# oled-control-panel.net
KiCad netlist of a schematic drawn in EAGLE
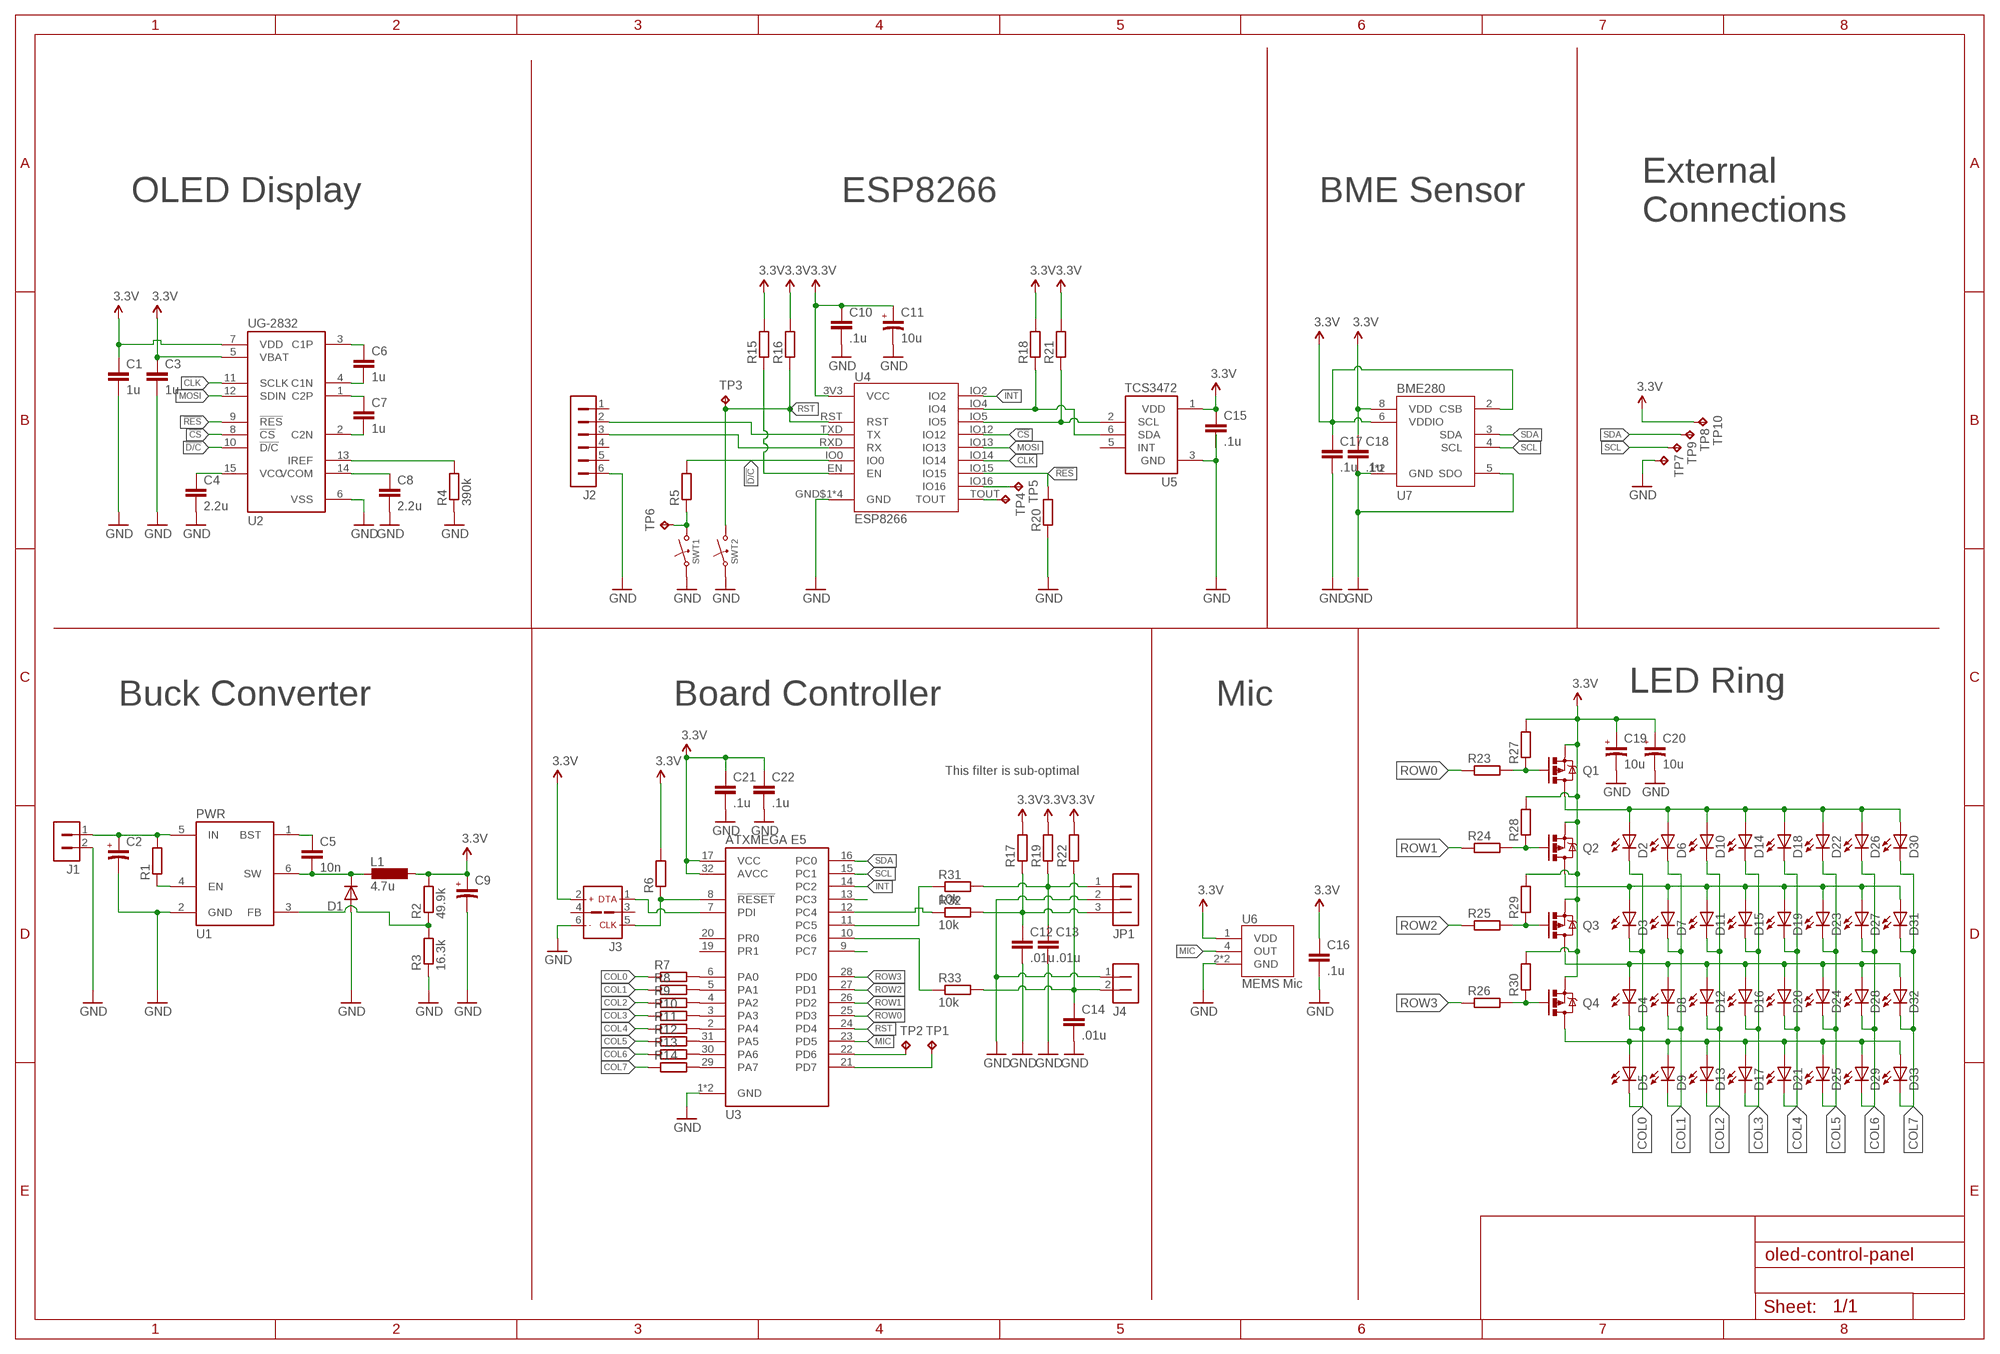
[diagram p0: schematic, sheet 1]

(export (version "E")
  (design (tool "Eeschema 10.0.6"))
  (components
    (comp (ref "C1")
      (value "1u")
      (footprint "eagle-import:0805")
      (libsource (lib "eagle-import") (part "C_0805"))
    )
    (comp (ref "C2")
      (value "C_POL_1206")
      (footprint "eagle-import:1206_POL")
      (libsource (lib "eagle-import") (part "C_POL_1206"))
    )
    (comp (ref "C3")
      (value "1u")
      (footprint "eagle-import:0805")
      (libsource (lib "eagle-import") (part "C_0805"))
    )
    (comp (ref "C4")
      (value "2.2u")
      (footprint "eagle-import:0805")
      (libsource (lib "eagle-import") (part "C_0805"))
    )
    (comp (ref "C5")
      (value "10n")
      (footprint "eagle-import:0805")
      (libsource (lib "eagle-import") (part "C_0805"))
    )
    (comp (ref "C6")
      (value "1u")
      (footprint "eagle-import:0805")
      (libsource (lib "eagle-import") (part "C_0805"))
    )
    (comp (ref "C7")
      (value "1u")
      (footprint "eagle-import:0805")
      (libsource (lib "eagle-import") (part "C_0805"))
    )
    (comp (ref "C8")
      (value "2.2u")
      (footprint "eagle-import:0805")
      (libsource (lib "eagle-import") (part "C_0805"))
    )
    (comp (ref "C9")
      (value "C_POL_1206")
      (footprint "eagle-import:1206_POL")
      (libsource (lib "eagle-import") (part "C_POL_1206"))
    )
    (comp (ref "C10")
      (value ".1u")
      (footprint "eagle-import:0603")
      (libsource (lib "eagle-import") (part "C_0603"))
    )
    (comp (ref "C11")
      (value "10u")
      (footprint "eagle-import:1206_POL")
      (libsource (lib "eagle-import") (part "C_POL_1206"))
    )
    (comp (ref "C12")
      (value ".01u")
      (footprint "eagle-import:0805")
      (libsource (lib "eagle-import") (part "C_0805"))
    )
    (comp (ref "C13")
      (value ".01u")
      (footprint "eagle-import:0805")
      (libsource (lib "eagle-import") (part "C_0805"))
    )
    (comp (ref "C14")
      (value ".01u")
      (footprint "eagle-import:0805")
      (libsource (lib "eagle-import") (part "C_0805"))
    )
    (comp (ref "C15")
      (value ".1u")
      (footprint "eagle-import:0603")
      (libsource (lib "eagle-import") (part "C_0603"))
    )
    (comp (ref "C16")
      (value ".1u")
      (footprint "eagle-import:0603")
      (libsource (lib "eagle-import") (part "C_0603"))
    )
    (comp (ref "C17")
      (value ".1u")
      (footprint "eagle-import:0603")
      (libsource (lib "eagle-import") (part "C_0603"))
    )
    (comp (ref "C18")
      (value ".1u")
      (footprint "eagle-import:0603")
      (libsource (lib "eagle-import") (part "C_0603"))
    )
    (comp (ref "C19")
      (value "10u")
      (footprint "eagle-import:1206_POL")
      (libsource (lib "eagle-import") (part "C_POL_1206"))
    )
    (comp (ref "C20")
      (value "10u")
      (footprint "eagle-import:1206_POL")
      (libsource (lib "eagle-import") (part "C_POL_1206"))
    )
    (comp (ref "C21")
      (value ".1u")
      (footprint "eagle-import:0603")
      (libsource (lib "eagle-import") (part "C_0603"))
    )
    (comp (ref "C22")
      (value ".1u")
      (footprint "eagle-import:0603")
      (libsource (lib "eagle-import") (part "C_0603"))
    )
    (comp (ref "D1")
      (value "D_FM581X")
      (footprint "eagle-import:DO-214AC")
      (libsource (lib "eagle-import") (part "D_FM581X"))
    )
    (comp (ref "D2")
      (value "LED_0805")
      (footprint "eagle-import:0805_LED")
      (libsource (lib "eagle-import") (part "LED_0805"))
    )
    (comp (ref "D3")
      (value "LED_0805")
      (footprint "eagle-import:0805_LED")
      (libsource (lib "eagle-import") (part "LED_0805"))
    )
    (comp (ref "D4")
      (value "LED_0805")
      (footprint "eagle-import:0805_LED")
      (libsource (lib "eagle-import") (part "LED_0805"))
    )
    (comp (ref "D5")
      (value "LED_0805")
      (footprint "eagle-import:0805_LED")
      (libsource (lib "eagle-import") (part "LED_0805"))
    )
    (comp (ref "D6")
      (value "LED_0805")
      (footprint "eagle-import:0805_LED")
      (libsource (lib "eagle-import") (part "LED_0805"))
    )
    (comp (ref "D7")
      (value "LED_0805")
      (footprint "eagle-import:0805_LED")
      (libsource (lib "eagle-import") (part "LED_0805"))
    )
    (comp (ref "D8")
      (value "LED_0805")
      (footprint "eagle-import:0805_LED")
      (libsource (lib "eagle-import") (part "LED_0805"))
    )
    (comp (ref "D9")
      (value "LED_0805")
      (footprint "eagle-import:0805_LED")
      (libsource (lib "eagle-import") (part "LED_0805"))
    )
    (comp (ref "D10")
      (value "LED_0805")
      (footprint "eagle-import:0805_LED")
      (libsource (lib "eagle-import") (part "LED_0805"))
    )
    (comp (ref "D11")
      (value "LED_0805")
      (footprint "eagle-import:0805_LED")
      (libsource (lib "eagle-import") (part "LED_0805"))
    )
    (comp (ref "D12")
      (value "LED_0805")
      (footprint "eagle-import:0805_LED")
      (libsource (lib "eagle-import") (part "LED_0805"))
    )
    (comp (ref "D13")
      (value "LED_0805")
      (footprint "eagle-import:0805_LED")
      (libsource (lib "eagle-import") (part "LED_0805"))
    )
    (comp (ref "D14")
      (value "LED_0805")
      (footprint "eagle-import:0805_LED")
      (libsource (lib "eagle-import") (part "LED_0805"))
    )
    (comp (ref "D15")
      (value "LED_0805")
      (footprint "eagle-import:0805_LED")
      (libsource (lib "eagle-import") (part "LED_0805"))
    )
    (comp (ref "D16")
      (value "LED_0805")
      (footprint "eagle-import:0805_LED")
      (libsource (lib "eagle-import") (part "LED_0805"))
    )
    (comp (ref "D17")
      (value "LED_0805")
      (footprint "eagle-import:0805_LED")
      (libsource (lib "eagle-import") (part "LED_0805"))
    )
    (comp (ref "D18")
      (value "LED_0805")
      (footprint "eagle-import:0805_LED")
      (libsource (lib "eagle-import") (part "LED_0805"))
    )
    (comp (ref "D19")
      (value "LED_0805")
      (footprint "eagle-import:0805_LED")
      (libsource (lib "eagle-import") (part "LED_0805"))
    )
    (comp (ref "D20")
      (value "LED_0805")
      (footprint "eagle-import:0805_LED")
      (libsource (lib "eagle-import") (part "LED_0805"))
    )
    (comp (ref "D21")
      (value "LED_0805")
      (footprint "eagle-import:0805_LED")
      (libsource (lib "eagle-import") (part "LED_0805"))
    )
    (comp (ref "D22")
      (value "LED_0805")
      (footprint "eagle-import:0805_LED")
      (libsource (lib "eagle-import") (part "LED_0805"))
    )
    (comp (ref "D23")
      (value "LED_0805")
      (footprint "eagle-import:0805_LED")
      (libsource (lib "eagle-import") (part "LED_0805"))
    )
    (comp (ref "D24")
      (value "LED_0805")
      (footprint "eagle-import:0805_LED")
      (libsource (lib "eagle-import") (part "LED_0805"))
    )
    (comp (ref "D25")
      (value "LED_0805")
      (footprint "eagle-import:0805_LED")
      (libsource (lib "eagle-import") (part "LED_0805"))
    )
    (comp (ref "D26")
      (value "LED_0805")
      (footprint "eagle-import:0805_LED")
      (libsource (lib "eagle-import") (part "LED_0805"))
    )
    (comp (ref "D27")
      (value "LED_0805")
      (footprint "eagle-import:0805_LED")
      (libsource (lib "eagle-import") (part "LED_0805"))
    )
    (comp (ref "D28")
      (value "LED_0805")
      (footprint "eagle-import:0805_LED")
      (libsource (lib "eagle-import") (part "LED_0805"))
    )
    (comp (ref "D29")
      (value "LED_0805")
      (footprint "eagle-import:0805_LED")
      (libsource (lib "eagle-import") (part "LED_0805"))
    )
    (comp (ref "D30")
      (value "LED_0805")
      (footprint "eagle-import:0805_LED")
      (libsource (lib "eagle-import") (part "LED_0805"))
    )
    (comp (ref "D31")
      (value "LED_0805")
      (footprint "eagle-import:0805_LED")
      (libsource (lib "eagle-import") (part "LED_0805"))
    )
    (comp (ref "D32")
      (value "LED_0805")
      (footprint "eagle-import:0805_LED")
      (libsource (lib "eagle-import") (part "LED_0805"))
    )
    (comp (ref "D33")
      (value "LED_0805")
      (footprint "eagle-import:0805_LED")
      (libsource (lib "eagle-import") (part "LED_0805"))
    )
    (comp (ref "J1")
      (value "1X2_MOLEX_53254")
      (footprint "eagle-import:1X2_MOLEX_53254")
      (libsource (lib "eagle-import") (part "1X2_MOLEX_53254"))
    )
    (comp (ref "J2")
      (value "1X6_SMD_RIGHT")
      (footprint "eagle-import:1X6_SMD_RIGHT")
      (libsource (lib "eagle-import") (part "1X6_SMD_RIGHT"))
    )
    (comp (ref "J3")
      (value "PDI_SMD")
      (footprint "eagle-import:ISP_SMD")
      (libsource (lib "eagle-import") (part "PDI_SMD"))
    )
    (comp (ref "J4")
      (value "1X2_MOLEX_53254")
      (footprint "eagle-import:1X2_MOLEX_53254")
      (libsource (lib "eagle-import") (part "1X2_MOLEX_53254"))
    )
    (comp (ref "JP1")
      (value "1X3_MOLEX_53254")
      (footprint "eagle-import:1X3_MOLEX_53254")
      (libsource (lib "eagle-import") (part "1X3_MOLEX_53254"))
    )
    (comp (ref "L1")
      (value "4.7u")
      (footprint "eagle-import:1210")
      (libsource (lib "eagle-import") (part "L_1210"))
    )
    (comp (ref "Q1")
      (value "PMV160UP")
      (footprint "eagle-import:SOT23")
      (libsource (lib "eagle-import") (part "PMV160UP"))
    )
    (comp (ref "Q2")
      (value "PMV160UP")
      (footprint "eagle-import:SOT23")
      (libsource (lib "eagle-import") (part "PMV160UP"))
    )
    (comp (ref "Q3")
      (value "PMV160UP")
      (footprint "eagle-import:SOT23")
      (libsource (lib "eagle-import") (part "PMV160UP"))
    )
    (comp (ref "Q4")
      (value "PMV160UP")
      (footprint "eagle-import:SOT23")
      (libsource (lib "eagle-import") (part "PMV160UP"))
    )
    (comp (ref "R1")
      (value "R_0805")
      (footprint "eagle-import:0805")
      (libsource (lib "eagle-import") (part "R_0805"))
    )
    (comp (ref "R2")
      (value "49.9k")
      (footprint "eagle-import:0805")
      (libsource (lib "eagle-import") (part "R_0805"))
    )
    (comp (ref "R3")
      (value "16.3k")
      (footprint "eagle-import:0805")
      (libsource (lib "eagle-import") (part "R_0805"))
    )
    (comp (ref "R4")
      (value "390k")
      (footprint "eagle-import:0805")
      (libsource (lib "eagle-import") (part "R_0805"))
    )
    (comp (ref "R5")
      (value "R_0603")
      (footprint "eagle-import:0603")
      (libsource (lib "eagle-import") (part "R_0603"))
    )
    (comp (ref "R6")
      (value "R_0603")
      (footprint "eagle-import:0603")
      (libsource (lib "eagle-import") (part "R_0603"))
    )
    (comp (ref "R7")
      (value "R_0603")
      (footprint "eagle-import:0603")
      (libsource (lib "eagle-import") (part "R_0603"))
    )
    (comp (ref "R8")
      (value "R_0603")
      (footprint "eagle-import:0603")
      (libsource (lib "eagle-import") (part "R_0603"))
    )
    (comp (ref "R9")
      (value "R_0603")
      (footprint "eagle-import:0603")
      (libsource (lib "eagle-import") (part "R_0603"))
    )
    (comp (ref "R10")
      (value "R_0603")
      (footprint "eagle-import:0603")
      (libsource (lib "eagle-import") (part "R_0603"))
    )
    (comp (ref "R11")
      (value "R_0603")
      (footprint "eagle-import:0603")
      (libsource (lib "eagle-import") (part "R_0603"))
    )
    (comp (ref "R12")
      (value "R_0603")
      (footprint "eagle-import:0603")
      (libsource (lib "eagle-import") (part "R_0603"))
    )
    (comp (ref "R13")
      (value "R_0603")
      (footprint "eagle-import:0603")
      (libsource (lib "eagle-import") (part "R_0603"))
    )
    (comp (ref "R14")
      (value "R_0603")
      (footprint "eagle-import:0603")
      (libsource (lib "eagle-import") (part "R_0603"))
    )
    (comp (ref "R15")
      (value "R_0603")
      (footprint "eagle-import:0603")
      (libsource (lib "eagle-import") (part "R_0603"))
    )
    (comp (ref "R16")
      (value "R_0603")
      (footprint "eagle-import:0603")
      (libsource (lib "eagle-import") (part "R_0603"))
    )
    (comp (ref "R17")
      (value "R_0603")
      (footprint "eagle-import:0603")
      (libsource (lib "eagle-import") (part "R_0603"))
    )
    (comp (ref "R18")
      (value "R_0603")
      (footprint "eagle-import:0603")
      (libsource (lib "eagle-import") (part "R_0603"))
    )
    (comp (ref "R19")
      (value "R_0603")
      (footprint "eagle-import:0603")
      (libsource (lib "eagle-import") (part "R_0603"))
    )
    (comp (ref "R20")
      (value "R_0603")
      (footprint "eagle-import:0603")
      (libsource (lib "eagle-import") (part "R_0603"))
    )
    (comp (ref "R21")
      (value "R_0603")
      (footprint "eagle-import:0603")
      (libsource (lib "eagle-import") (part "R_0603"))
    )
    (comp (ref "R22")
      (value "R_0603")
      (footprint "eagle-import:0603")
      (libsource (lib "eagle-import") (part "R_0603"))
    )
    (comp (ref "R23")
      (value "R_0603")
      (footprint "eagle-import:0603")
      (libsource (lib "eagle-import") (part "R_0603"))
    )
    (comp (ref "R24")
      (value "R_0603")
      (footprint "eagle-import:0603")
      (libsource (lib "eagle-import") (part "R_0603"))
    )
    (comp (ref "R25")
      (value "R_0603")
      (footprint "eagle-import:0603")
      (libsource (lib "eagle-import") (part "R_0603"))
    )
    (comp (ref "R26")
      (value "R_0603")
      (footprint "eagle-import:0603")
      (libsource (lib "eagle-import") (part "R_0603"))
    )
    (comp (ref "R27")
      (value "R_0603")
      (footprint "eagle-import:0603")
      (libsource (lib "eagle-import") (part "R_0603"))
    )
    (comp (ref "R28")
      (value "R_0603")
      (footprint "eagle-import:0603")
      (libsource (lib "eagle-import") (part "R_0603"))
    )
    (comp (ref "R29")
      (value "R_0603")
      (footprint "eagle-import:0603")
      (libsource (lib "eagle-import") (part "R_0603"))
    )
    (comp (ref "R30")
      (value "R_0603")
      (footprint "eagle-import:0603")
      (libsource (lib "eagle-import") (part "R_0603"))
    )
    (comp (ref "R31")
      (value "10k")
      (footprint "eagle-import:0603")
      (libsource (lib "eagle-import") (part "R_0603"))
    )
    (comp (ref "R32")
      (value "10k")
      (footprint "eagle-import:0603")
      (libsource (lib "eagle-import") (part "R_0603"))
    )
    (comp (ref "R33")
      (value "10k")
      (footprint "eagle-import:0603")
      (libsource (lib "eagle-import") (part "R_0603"))
    )
    (comp (ref "SWT1")
      (value "BUTTON_SMD_2P")
      (footprint "eagle-import:BTN_SMD_2PIN")
      (libsource (lib "eagle-import") (part "BUTTON_SMD_2P"))
    )
    (comp (ref "SWT2")
      (value "BUTTON_SMD_2P")
      (footprint "eagle-import:BTN_SMD_2PIN")
      (libsource (lib "eagle-import") (part "BUTTON_SMD_2P"))
    )
    (comp (ref "TP1")
      (value "TPTP15R")
      (footprint "eagle-import:TP15R")
      (libsource (lib "eagle-import") (part "TPTP15R"))
    )
    (comp (ref "TP2")
      (value "TPTP15R")
      (footprint "eagle-import:TP15R")
      (libsource (lib "eagle-import") (part "TPTP15R"))
    )
    (comp (ref "TP3")
      (value "TPTP15R")
      (footprint "eagle-import:TP15R")
      (libsource (lib "eagle-import") (part "TPTP15R"))
    )
    (comp (ref "TP4")
      (value "TPTP15R")
      (footprint "eagle-import:TP15R")
      (libsource (lib "eagle-import") (part "TPTP15R"))
    )
    (comp (ref "TP5")
      (value "TPTP15R")
      (footprint "eagle-import:TP15R")
      (libsource (lib "eagle-import") (part "TPTP15R"))
    )
    (comp (ref "TP6")
      (value "TPTP15R")
      (footprint "eagle-import:TP15R")
      (libsource (lib "eagle-import") (part "TPTP15R"))
    )
    (comp (ref "TP7")
      (value "TPTP15R")
      (footprint "eagle-import:TP15R")
      (libsource (lib "eagle-import") (part "TPTP15R"))
    )
    (comp (ref "TP8")
      (value "TPTP15R")
      (footprint "eagle-import:TP15R")
      (libsource (lib "eagle-import") (part "TPTP15R"))
    )
    (comp (ref "TP9")
      (value "TPTP15R")
      (footprint "eagle-import:TP15R")
      (libsource (lib "eagle-import") (part "TPTP15R"))
    )
    (comp (ref "TP10")
      (value "TPTP15R")
      (footprint "eagle-import:TP15R")
      (libsource (lib "eagle-import") (part "TPTP15R"))
    )
    (comp (ref "U1")
      (value "AP3211")
      (footprint "eagle-import:SOT23-6")
      (libsource (lib "eagle-import") (part "AP3211"))
    )
    (comp (ref "U2")
      (value "UG-2832HSWEG04")
      (footprint "eagle-import:UG-2832HSWEG04")
      (libsource (lib "eagle-import") (part "UG-2832HSWEG04"))
    )
    (comp (ref "U3")
      (value "ATXMEGA_E5_TQFP")
      (footprint "eagle-import:TQFP32")
      (libsource (lib "eagle-import") (part "ATXMEGA_E5_TQFP"))
    )
    (comp (ref "U4")
      (value "ESP8266_13")
      (footprint "eagle-import:ESP13")
      (libsource (lib "eagle-import") (part "ESP8266_13"))
    )
    (comp (ref "U5")
      (value "TCS3472")
      (footprint "eagle-import:TCS3472")
      (libsource (lib "eagle-import") (part "TCS3472"))
    )
    (comp (ref "U6")
      (value "SPW2430HR5H_B")
      (footprint "eagle-import:SPW2430HR5H_B")
      (libsource (lib "eagle-import") (part "SPW2430HR5H_B"))
    )
    (comp (ref "U7")
      (value "BME280")
      (footprint "eagle-import:BME280")
      (libsource (lib "eagle-import") (part "BME280"))
    )
  )
  (nets
    (net (code "1") (name "/~{CS}") (class "Default")
      (node (ref "U2") (pin "8") (pinfunction "~{CS}_8") (pintype "bidirectional"))
      (node (ref "U4") (pin "IO12") (pinfunction "IO12_IO12") (pintype "bidirectional"))
    )
    (net (code "2") (name "/~{D{slash}C}") (class "Default")
      (node (ref "R5") (pin "2") (pinfunction "2_2") (pintype "passive"))
      (node (ref "U2") (pin "10") (pinfunction "~{D/C}_10") (pintype "bidirectional"))
      (node (ref "U4") (pin "IO0") (pinfunction "IO0_IO0") (pintype "bidirectional"))
    )
    (net (code "3") (name "/~{RES}") (class "Default")
      (node (ref "R20") (pin "2") (pinfunction "2_2") (pintype "passive"))
      (node (ref "U2") (pin "9") (pinfunction "~{RES}_9") (pintype "bidirectional"))
      (node (ref "U4") (pin "IO15") (pinfunction "IO15_IO15") (pintype "bidirectional"))
    )
    (net (code "4") (name "3.3V") (class "Default")
      (node (ref "C1") (pin "1") (pinfunction "1_1") (pintype "passive"))
      (node (ref "C10") (pin "1") (pinfunction "1_1") (pintype "passive"))
      (node (ref "C11") (pin "1") (pinfunction "1_1") (pintype "passive"))
      (node (ref "C15") (pin "1") (pinfunction "1_1") (pintype "passive"))
      (node (ref "C16") (pin "1") (pinfunction "1_1") (pintype "passive"))
      (node (ref "C17") (pin "1") (pinfunction "1_1") (pintype "passive"))
      (node (ref "C18") (pin "1") (pinfunction "1_1") (pintype "passive"))
      (node (ref "C19") (pin "1") (pinfunction "1_1") (pintype "passive"))
      (node (ref "C20") (pin "1") (pinfunction "1_1") (pintype "passive"))
      (node (ref "C21") (pin "1") (pinfunction "1_1") (pintype "passive"))
      (node (ref "C22") (pin "1") (pinfunction "1_1") (pintype "passive"))
      (node (ref "C3") (pin "1") (pinfunction "1_1") (pintype "passive"))
      (node (ref "C9") (pin "1") (pinfunction "1_1") (pintype "passive"))
      (node (ref "J3") (pin "2") (pinfunction "VCC_2") (pintype "bidirectional"))
      (node (ref "L1") (pin "2") (pinfunction "2_2") (pintype "passive"))
      (node (ref "Q1") (pin "2") (pinfunction "S_2") (pintype "passive"))
      (node (ref "Q2") (pin "2") (pinfunction "S_2") (pintype "passive"))
      (node (ref "Q3") (pin "2") (pinfunction "S_2") (pintype "passive"))
      (node (ref "Q4") (pin "2") (pinfunction "S_2") (pintype "passive"))
      (node (ref "R15") (pin "2") (pinfunction "2_2") (pintype "passive"))
      (node (ref "R16") (pin "2") (pinfunction "2_2") (pintype "passive"))
      (node (ref "R17") (pin "2") (pinfunction "2_2") (pintype "passive"))
      (node (ref "R18") (pin "2") (pinfunction "2_2") (pintype "passive"))
      (node (ref "R19") (pin "2") (pinfunction "2_2") (pintype "passive"))
      (node (ref "R2") (pin "2") (pinfunction "2_2") (pintype "passive"))
      (node (ref "R21") (pin "2") (pinfunction "2_2") (pintype "passive"))
      (node (ref "R22") (pin "2") (pinfunction "2_2") (pintype "passive"))
      (node (ref "R27") (pin "2") (pinfunction "2_2") (pintype "passive"))
      (node (ref "R28") (pin "2") (pinfunction "2_2") (pintype "passive"))
      (node (ref "R29") (pin "2") (pinfunction "2_2") (pintype "passive"))
      (node (ref "R30") (pin "2") (pinfunction "2_2") (pintype "passive"))
      (node (ref "R6") (pin "2") (pinfunction "2_2") (pintype "passive"))
      (node (ref "TP10") (pin "TP") (pinfunction "TP_TP") (pintype "input"))
      (node (ref "U2") (pin "5") (pinfunction "VBAT_5") (pintype "bidirectional"))
      (node (ref "U2") (pin "7") (pinfunction "VDD_7") (pintype "bidirectional"))
      (node (ref "U3") (pin "17") (pinfunction "VCC_17") (pintype "bidirectional"))
      (node (ref "U3") (pin "32") (pinfunction "AVCC_32") (pintype "bidirectional"))
      (node (ref "U4") (pin "3V3") (pinfunction "VCC_3V3") (pintype "bidirectional"))
      (node (ref "U5") (pin "1") (pinfunction "VDD_1") (pintype "bidirectional"))
      (node (ref "U6") (pin "1") (pinfunction "VDD_1") (pintype "bidirectional"))
      (node (ref "U7") (pin "2") (pinfunction "CSB_2") (pintype "bidirectional"))
      (node (ref "U7") (pin "6") (pinfunction "VDDIO_6") (pintype "bidirectional"))
      (node (ref "U7") (pin "8") (pinfunction "VDD_8") (pintype "bidirectional"))
    )
    (net (code "5") (name "CLK") (class "Default")
      (node (ref "U2") (pin "11") (pinfunction "SCLK_11") (pintype "bidirectional"))
      (node (ref "U4") (pin "IO14") (pinfunction "IO14_IO14") (pintype "bidirectional"))
    )
    (net (code "6") (name "COL0") (class "Default")
      (node (ref "D2") (pin "C") (pinfunction "C_C") (pintype "passive"))
      (node (ref "D3") (pin "C") (pinfunction "C_C") (pintype "passive"))
      (node (ref "D4") (pin "C") (pinfunction "C_C") (pintype "passive"))
      (node (ref "D5") (pin "C") (pinfunction "C_C") (pintype "passive"))
      (node (ref "R7") (pin "1") (pinfunction "1_1") (pintype "passive"))
    )
    (net (code "7") (name "COL1") (class "Default")
      (node (ref "D6") (pin "C") (pinfunction "C_C") (pintype "passive"))
      (node (ref "D7") (pin "C") (pinfunction "C_C") (pintype "passive"))
      (node (ref "D8") (pin "C") (pinfunction "C_C") (pintype "passive"))
      (node (ref "D9") (pin "C") (pinfunction "C_C") (pintype "passive"))
      (node (ref "R8") (pin "1") (pinfunction "1_1") (pintype "passive"))
    )
    (net (code "8") (name "COL2") (class "Default")
      (node (ref "D10") (pin "C") (pinfunction "C_C") (pintype "passive"))
      (node (ref "D11") (pin "C") (pinfunction "C_C") (pintype "passive"))
      (node (ref "D12") (pin "C") (pinfunction "C_C") (pintype "passive"))
      (node (ref "D13") (pin "C") (pinfunction "C_C") (pintype "passive"))
      (node (ref "R9") (pin "1") (pinfunction "1_1") (pintype "passive"))
    )
    (net (code "9") (name "COL3") (class "Default")
      (node (ref "D14") (pin "C") (pinfunction "C_C") (pintype "passive"))
      (node (ref "D15") (pin "C") (pinfunction "C_C") (pintype "passive"))
      (node (ref "D16") (pin "C") (pinfunction "C_C") (pintype "passive"))
      (node (ref "D17") (pin "C") (pinfunction "C_C") (pintype "passive"))
      (node (ref "R10") (pin "1") (pinfunction "1_1") (pintype "passive"))
    )
    (net (code "10") (name "COL4") (class "Default")
      (node (ref "D18") (pin "C") (pinfunction "C_C") (pintype "passive"))
      (node (ref "D19") (pin "C") (pinfunction "C_C") (pintype "passive"))
      (node (ref "D20") (pin "C") (pinfunction "C_C") (pintype "passive"))
      (node (ref "D21") (pin "C") (pinfunction "C_C") (pintype "passive"))
      (node (ref "R11") (pin "1") (pinfunction "1_1") (pintype "passive"))
    )
    (net (code "11") (name "COL5") (class "Default")
      (node (ref "D22") (pin "C") (pinfunction "C_C") (pintype "passive"))
      (node (ref "D23") (pin "C") (pinfunction "C_C") (pintype "passive"))
      (node (ref "D24") (pin "C") (pinfunction "C_C") (pintype "passive"))
      (node (ref "D25") (pin "C") (pinfunction "C_C") (pintype "passive"))
      (node (ref "R12") (pin "1") (pinfunction "1_1") (pintype "passive"))
    )
    (net (code "12") (name "COL6") (class "Default")
      (node (ref "D26") (pin "C") (pinfunction "C_C") (pintype "passive"))
      (node (ref "D27") (pin "C") (pinfunction "C_C") (pintype "passive"))
      (node (ref "D28") (pin "C") (pinfunction "C_C") (pintype "passive"))
      (node (ref "D29") (pin "C") (pinfunction "C_C") (pintype "passive"))
      (node (ref "R13") (pin "1") (pinfunction "1_1") (pintype "passive"))
    )
    (net (code "13") (name "COL7") (class "Default")
      (node (ref "D30") (pin "C") (pinfunction "C_C") (pintype "passive"))
      (node (ref "D31") (pin "C") (pinfunction "C_C") (pintype "passive"))
      (node (ref "D32") (pin "C") (pinfunction "C_C") (pintype "passive"))
      (node (ref "D33") (pin "C") (pinfunction "C_C") (pintype "passive"))
      (node (ref "R14") (pin "1") (pinfunction "1_1") (pintype "passive"))
    )
    (net (code "14") (name "GND") (class "Default")
      (node (ref "C1") (pin "2") (pinfunction "2_2") (pintype "passive"))
      (node (ref "C10") (pin "2") (pinfunction "2_2") (pintype "passive"))
      (node (ref "C11") (pin "2") (pinfunction "2_2") (pintype "passive"))
      (node (ref "C12") (pin "2") (pinfunction "2_2") (pintype "passive"))
      (node (ref "C13") (pin "2") (pinfunction "2_2") (pintype "passive"))
      (node (ref "C14") (pin "2") (pinfunction "2_2") (pintype "passive"))
      (node (ref "C15") (pin "2") (pinfunction "2_2") (pintype "passive"))
      (node (ref "C16") (pin "2") (pinfunction "2_2") (pintype "passive"))
      (node (ref "C17") (pin "2") (pinfunction "2_2") (pintype "passive"))
      (node (ref "C18") (pin "2") (pinfunction "2_2") (pintype "passive"))
      (node (ref "C19") (pin "2") (pinfunction "2_2") (pintype "passive"))
      (node (ref "C2") (pin "2") (pinfunction "2_2") (pintype "passive"))
      (node (ref "C20") (pin "2") (pinfunction "2_2") (pintype "passive"))
      (node (ref "C21") (pin "2") (pinfunction "2_2") (pintype "passive"))
      (node (ref "C22") (pin "2") (pinfunction "2_2") (pintype "passive"))
      (node (ref "C3") (pin "2") (pinfunction "2_2") (pintype "passive"))
      (node (ref "C4") (pin "2") (pinfunction "2_2") (pintype "passive"))
      (node (ref "C8") (pin "2") (pinfunction "2_2") (pintype "passive"))
      (node (ref "C9") (pin "2") (pinfunction "2_2") (pintype "passive"))
      (node (ref "D1") (pin "A") (pinfunction "A_A") (pintype "passive"))
      (node (ref "J1") (pin "2") (pinfunction "2_2") (pintype "bidirectional"))
      (node (ref "J2") (pin "6") (pinfunction "6_6") (pintype "bidirectional"))
      (node (ref "J3") (pin "6") (pinfunction "GND_6") (pintype "bidirectional"))
      (node (ref "J4") (pin "1") (pinfunction "1_1") (pintype "bidirectional"))
      (node (ref "JP1") (pin "2") (pinfunction "2_2") (pintype "bidirectional"))
      (node (ref "R20") (pin "1") (pinfunction "1_1") (pintype "passive"))
      (node (ref "R3") (pin "1") (pinfunction "1_1") (pintype "passive"))
      (node (ref "R4") (pin "1") (pinfunction "1_1") (pintype "passive"))
      (node (ref "SWT1") (pin "1") (pinfunction "P$1_1") (pintype "bidirectional"))
      (node (ref "SWT2") (pin "1") (pinfunction "P$1_1") (pintype "bidirectional"))
      (node (ref "TP7") (pin "TP") (pinfunction "TP_TP") (pintype "input"))
      (node (ref "U1") (pin "2") (pinfunction "GND_2") (pintype "bidirectional"))
      (node (ref "U2") (pin "6") (pinfunction "VSS_6") (pintype "bidirectional"))
      (node (ref "U3") (pin "1") (pinfunction "GND_1") (pintype "bidirectional"))
      (node (ref "U3") (pin "18") (pinfunction "GND_18") (pintype "bidirectional"))
      (node (ref "U4") (pin "GND$1") (pinfunction "GND_GND$1") (pintype "bidirectional"))
      (node (ref "U4") (pin "GND$2") (pinfunction "GND_GND$2") (pintype "bidirectional"))
      (node (ref "U4") (pin "GND$3") (pinfunction "GND_GND$3") (pintype "bidirectional"))
      (node (ref "U4") (pin "GND$4") (pinfunction "GND_GND$4") (pintype "bidirectional"))
      (node (ref "U5") (pin "3") (pinfunction "GND_3") (pintype "bidirectional"))
      (node (ref "U6") (pin "2") (pinfunction "GND_2") (pintype "bidirectional"))
      (node (ref "U6") (pin "3") (pinfunction "GND_3") (pintype "bidirectional"))
      (node (ref "U7") (pin "1") (pinfunction "GND_1") (pintype "bidirectional"))
      (node (ref "U7") (pin "5") (pinfunction "SDO_5") (pintype "bidirectional"))
      (node (ref "U7") (pin "7") (pinfunction "GND_7") (pintype "bidirectional"))
    )
    (net (code "15") (name "INT") (class "Default")
      (node (ref "U3") (pin "14") (pinfunction "PC2_14") (pintype "bidirectional"))
      (node (ref "U4") (pin "IO2") (pinfunction "IO2_IO2") (pintype "bidirectional"))
    )
    (net (code "16") (name "MIC") (class "Default")
      (node (ref "U3") (pin "23") (pinfunction "PD5_23") (pintype "bidirectional"))
      (node (ref "U6") (pin "4") (pinfunction "OUT_4") (pintype "bidirectional"))
    )
    (net (code "17") (name "MOSI") (class "Default")
      (node (ref "U2") (pin "12") (pinfunction "SDIN_12") (pintype "bidirectional"))
      (node (ref "U4") (pin "IO13") (pinfunction "IO13_IO13") (pintype "bidirectional"))
    )
    (net (code "18") (name "Net-(C12-Pad1)") (class "Default")
      (node (ref "C12") (pin "1") (pinfunction "1_1") (pintype "passive"))
      (node (ref "JP1") (pin "3") (pinfunction "3_3") (pintype "bidirectional"))
      (node (ref "R17") (pin "1") (pinfunction "1_1") (pintype "passive"))
      (node (ref "R32") (pin "2") (pinfunction "2_2") (pintype "passive"))
    )
    (net (code "19") (name "Net-(C13-Pad1)") (class "Default")
      (node (ref "C13") (pin "1") (pinfunction "1_1") (pintype "passive"))
      (node (ref "JP1") (pin "1") (pinfunction "1_1") (pintype "bidirectional"))
      (node (ref "R19") (pin "1") (pinfunction "1_1") (pintype "passive"))
      (node (ref "R31") (pin "2") (pinfunction "2_2") (pintype "passive"))
    )
    (net (code "20") (name "Net-(C14-Pad1)") (class "Default")
      (node (ref "C14") (pin "1") (pinfunction "1_1") (pintype "passive"))
      (node (ref "J4") (pin "2") (pinfunction "2_2") (pintype "bidirectional"))
      (node (ref "R22") (pin "1") (pinfunction "1_1") (pintype "passive"))
      (node (ref "R33") (pin "2") (pinfunction "2_2") (pintype "passive"))
    )
    (net (code "21") (name "Net-(J3-CLK)") (class "Default")
      (node (ref "J3") (pin "5") (pinfunction "CLK_5") (pintype "bidirectional"))
      (node (ref "R6") (pin "1") (pinfunction "1_1") (pintype "passive"))
      (node (ref "U3") (pin "8") (pinfunction "~{RESET}_8") (pintype "bidirectional"))
    )
    (net (code "22") (name "Net-(J3-DATA)") (class "Default")
      (node (ref "J3") (pin "1") (pinfunction "DATA_1") (pintype "bidirectional"))
      (node (ref "U3") (pin "7") (pinfunction "PDI_7") (pintype "bidirectional"))
    )
    (net (code "23") (name "Net-(Q1-D)") (class "Default")
      (node (ref "D10") (pin "A") (pinfunction "A_A") (pintype "passive"))
      (node (ref "D14") (pin "A") (pinfunction "A_A") (pintype "passive"))
      (node (ref "D18") (pin "A") (pinfunction "A_A") (pintype "passive"))
      (node (ref "D2") (pin "A") (pinfunction "A_A") (pintype "passive"))
      (node (ref "D22") (pin "A") (pinfunction "A_A") (pintype "passive"))
      (node (ref "D26") (pin "A") (pinfunction "A_A") (pintype "passive"))
      (node (ref "D30") (pin "A") (pinfunction "A_A") (pintype "passive"))
      (node (ref "D6") (pin "A") (pinfunction "A_A") (pintype "passive"))
      (node (ref "Q1") (pin "3") (pinfunction "D_3") (pintype "passive"))
    )
    (net (code "24") (name "Net-(Q1-G)") (class "Default")
      (node (ref "Q1") (pin "1") (pinfunction "G_1") (pintype "passive"))
      (node (ref "R23") (pin "2") (pinfunction "2_2") (pintype "passive"))
      (node (ref "R27") (pin "1") (pinfunction "1_1") (pintype "passive"))
    )
    (net (code "25") (name "Net-(Q2-D)") (class "Default")
      (node (ref "D11") (pin "A") (pinfunction "A_A") (pintype "passive"))
      (node (ref "D15") (pin "A") (pinfunction "A_A") (pintype "passive"))
      (node (ref "D19") (pin "A") (pinfunction "A_A") (pintype "passive"))
      (node (ref "D23") (pin "A") (pinfunction "A_A") (pintype "passive"))
      (node (ref "D27") (pin "A") (pinfunction "A_A") (pintype "passive"))
      (node (ref "D3") (pin "A") (pinfunction "A_A") (pintype "passive"))
      (node (ref "D31") (pin "A") (pinfunction "A_A") (pintype "passive"))
      (node (ref "D7") (pin "A") (pinfunction "A_A") (pintype "passive"))
      (node (ref "Q2") (pin "3") (pinfunction "D_3") (pintype "passive"))
    )
    (net (code "26") (name "Net-(Q2-G)") (class "Default")
      (node (ref "Q2") (pin "1") (pinfunction "G_1") (pintype "passive"))
      (node (ref "R24") (pin "2") (pinfunction "2_2") (pintype "passive"))
      (node (ref "R28") (pin "1") (pinfunction "1_1") (pintype "passive"))
    )
    (net (code "27") (name "Net-(Q3-D)") (class "Default")
      (node (ref "D12") (pin "A") (pinfunction "A_A") (pintype "passive"))
      (node (ref "D16") (pin "A") (pinfunction "A_A") (pintype "passive"))
      (node (ref "D20") (pin "A") (pinfunction "A_A") (pintype "passive"))
      (node (ref "D24") (pin "A") (pinfunction "A_A") (pintype "passive"))
      (node (ref "D28") (pin "A") (pinfunction "A_A") (pintype "passive"))
      (node (ref "D32") (pin "A") (pinfunction "A_A") (pintype "passive"))
      (node (ref "D4") (pin "A") (pinfunction "A_A") (pintype "passive"))
      (node (ref "D8") (pin "A") (pinfunction "A_A") (pintype "passive"))
      (node (ref "Q3") (pin "3") (pinfunction "D_3") (pintype "passive"))
    )
    (net (code "28") (name "Net-(Q3-G)") (class "Default")
      (node (ref "Q3") (pin "1") (pinfunction "G_1") (pintype "passive"))
      (node (ref "R25") (pin "2") (pinfunction "2_2") (pintype "passive"))
      (node (ref "R29") (pin "1") (pinfunction "1_1") (pintype "passive"))
    )
    (net (code "29") (name "Net-(Q4-D)") (class "Default")
      (node (ref "D13") (pin "A") (pinfunction "A_A") (pintype "passive"))
      (node (ref "D17") (pin "A") (pinfunction "A_A") (pintype "passive"))
      (node (ref "D21") (pin "A") (pinfunction "A_A") (pintype "passive"))
      (node (ref "D25") (pin "A") (pinfunction "A_A") (pintype "passive"))
      (node (ref "D29") (pin "A") (pinfunction "A_A") (pintype "passive"))
      (node (ref "D33") (pin "A") (pinfunction "A_A") (pintype "passive"))
      (node (ref "D5") (pin "A") (pinfunction "A_A") (pintype "passive"))
      (node (ref "D9") (pin "A") (pinfunction "A_A") (pintype "passive"))
      (node (ref "Q4") (pin "3") (pinfunction "D_3") (pintype "passive"))
    )
    (net (code "30") (name "Net-(Q4-G)") (class "Default")
      (node (ref "Q4") (pin "1") (pinfunction "G_1") (pintype "passive"))
      (node (ref "R26") (pin "2") (pinfunction "2_2") (pintype "passive"))
      (node (ref "R30") (pin "1") (pinfunction "1_1") (pintype "passive"))
    )
    (net (code "31") (name "Net-(R15-Pad1)") (class "Default")
      (node (ref "R15") (pin "1") (pinfunction "1_1") (pintype "passive"))
      (node (ref "U4") (pin "EN") (pinfunction "EN_EN") (pintype "bidirectional"))
    )
    (net (code "32") (name "Net-(SWT1-P$2)") (class "Default")
      (node (ref "R5") (pin "1") (pinfunction "1_1") (pintype "passive"))
      (node (ref "SWT1") (pin "2") (pinfunction "P$2_2") (pintype "bidirectional"))
      (node (ref "TP6") (pin "TP") (pinfunction "TP_TP") (pintype "input"))
    )
    (net (code "33") (name "Net-(TP4-PadTP)") (class "Default")
      (node (ref "TP4") (pin "TP") (pinfunction "TP_TP") (pintype "input"))
      (node (ref "U4") (pin "TOUT") (pinfunction "TOUT_TOUT") (pintype "bidirectional"))
    )
    (net (code "34") (name "Net-(TP5-PadTP)") (class "Default")
      (node (ref "TP5") (pin "TP") (pinfunction "TP_TP") (pintype "input"))
      (node (ref "U4") (pin "IO16") (pinfunction "IO16_IO16") (pintype "bidirectional"))
    )
    (net (code "35") (name "Net-(U1-BST)") (class "Default")
      (node (ref "C5") (pin "1") (pinfunction "1_1") (pintype "passive"))
      (node (ref "U1") (pin "1") (pinfunction "BST_1") (pintype "bidirectional"))
    )
    (net (code "36") (name "Net-(U1-EN)") (class "Default")
      (node (ref "R1") (pin "1") (pinfunction "1_1") (pintype "passive"))
      (node (ref "U1") (pin "4") (pinfunction "EN_4") (pintype "bidirectional"))
    )
    (net (code "37") (name "Net-(U1-FB)") (class "Default")
      (node (ref "R2") (pin "1") (pinfunction "1_1") (pintype "passive"))
      (node (ref "R3") (pin "2") (pinfunction "2_2") (pintype "passive"))
      (node (ref "U1") (pin "3") (pinfunction "FB_3") (pintype "bidirectional"))
    )
    (net (code "38") (name "Net-(U1-IN)") (class "Default")
      (node (ref "C2") (pin "1") (pinfunction "1_1") (pintype "passive"))
      (node (ref "J1") (pin "1") (pinfunction "1_1") (pintype "bidirectional"))
      (node (ref "R1") (pin "2") (pinfunction "2_2") (pintype "passive"))
      (node (ref "U1") (pin "5") (pinfunction "IN_5") (pintype "bidirectional"))
    )
    (net (code "39") (name "Net-(U1-SW)") (class "Default")
      (node (ref "C5") (pin "2") (pinfunction "2_2") (pintype "passive"))
      (node (ref "D1") (pin "C") (pinfunction "C_C") (pintype "passive"))
      (node (ref "L1") (pin "1") (pinfunction "1_1") (pintype "passive"))
      (node (ref "U1") (pin "6") (pinfunction "SW_6") (pintype "bidirectional"))
    )
    (net (code "40") (name "Net-(U2-C1N)") (class "Default")
      (node (ref "C6") (pin "2") (pinfunction "2_2") (pintype "passive"))
      (node (ref "U2") (pin "4") (pinfunction "C1N_4") (pintype "bidirectional"))
    )
    (net (code "41") (name "Net-(U2-C1P)") (class "Default")
      (node (ref "C6") (pin "1") (pinfunction "1_1") (pintype "passive"))
      (node (ref "U2") (pin "3") (pinfunction "C1P_3") (pintype "bidirectional"))
    )
    (net (code "42") (name "Net-(U2-C2N)") (class "Default")
      (node (ref "C7") (pin "2") (pinfunction "2_2") (pintype "passive"))
      (node (ref "U2") (pin "2") (pinfunction "C2N_2") (pintype "bidirectional"))
    )
    (net (code "43") (name "Net-(U2-C2P)") (class "Default")
      (node (ref "C7") (pin "1") (pinfunction "1_1") (pintype "passive"))
      (node (ref "U2") (pin "1") (pinfunction "C2P_1") (pintype "bidirectional"))
    )
    (net (code "44") (name "Net-(U2-IREF)") (class "Default")
      (node (ref "R4") (pin "2") (pinfunction "2_2") (pintype "passive"))
      (node (ref "U2") (pin "13") (pinfunction "IREF_13") (pintype "bidirectional"))
    )
    (net (code "45") (name "Net-(U2-VCC)") (class "Default")
      (node (ref "C4") (pin "1") (pinfunction "1_1") (pintype "passive"))
      (node (ref "U2") (pin "15") (pinfunction "VCC_15") (pintype "bidirectional"))
    )
    (net (code "46") (name "Net-(U2-VCOM)") (class "Default")
      (node (ref "C8") (pin "1") (pinfunction "1_1") (pintype "passive"))
      (node (ref "U2") (pin "14") (pinfunction "VCOM_14") (pintype "bidirectional"))
    )
    (net (code "47") (name "Net-(U3-PA0)") (class "Default")
      (node (ref "R7") (pin "2") (pinfunction "2_2") (pintype "passive"))
      (node (ref "U3") (pin "6") (pinfunction "PA0_6") (pintype "bidirectional"))
    )
    (net (code "48") (name "Net-(U3-PA1)") (class "Default")
      (node (ref "R8") (pin "2") (pinfunction "2_2") (pintype "passive"))
      (node (ref "U3") (pin "5") (pinfunction "PA1_5") (pintype "bidirectional"))
    )
    (net (code "49") (name "Net-(U3-PA2)") (class "Default")
      (node (ref "R9") (pin "2") (pinfunction "2_2") (pintype "passive"))
      (node (ref "U3") (pin "4") (pinfunction "PA2_4") (pintype "bidirectional"))
    )
    (net (code "50") (name "Net-(U3-PA3)") (class "Default")
      (node (ref "R10") (pin "2") (pinfunction "2_2") (pintype "passive"))
      (node (ref "U3") (pin "3") (pinfunction "PA3_3") (pintype "bidirectional"))
    )
    (net (code "51") (name "Net-(U3-PA4)") (class "Default")
      (node (ref "R11") (pin "2") (pinfunction "2_2") (pintype "passive"))
      (node (ref "U3") (pin "2") (pinfunction "PA4_2") (pintype "bidirectional"))
    )
    (net (code "52") (name "Net-(U3-PA5)") (class "Default")
      (node (ref "R12") (pin "2") (pinfunction "2_2") (pintype "passive"))
      (node (ref "U3") (pin "31") (pinfunction "PA5_31") (pintype "bidirectional"))
    )
    (net (code "53") (name "Net-(U3-PA6)") (class "Default")
      (node (ref "R13") (pin "2") (pinfunction "2_2") (pintype "passive"))
      (node (ref "U3") (pin "30") (pinfunction "PA6_30") (pintype "bidirectional"))
    )
    (net (code "54") (name "Net-(U3-PA7)") (class "Default")
      (node (ref "R14") (pin "2") (pinfunction "2_2") (pintype "passive"))
      (node (ref "U3") (pin "29") (pinfunction "PA7_29") (pintype "bidirectional"))
    )
    (net (code "55") (name "Net-(U3-PC4)") (class "Default")
      (node (ref "R32") (pin "1") (pinfunction "1_1") (pintype "passive"))
      (node (ref "U3") (pin "12") (pinfunction "PC4_12") (pintype "bidirectional"))
    )
    (net (code "56") (name "Net-(U3-PC5)") (class "Default")
      (node (ref "R31") (pin "1") (pinfunction "1_1") (pintype "passive"))
      (node (ref "U3") (pin "11") (pinfunction "PC5_11") (pintype "bidirectional"))
    )
    (net (code "57") (name "Net-(U3-PC6)") (class "Default")
      (node (ref "R33") (pin "1") (pinfunction "1_1") (pintype "passive"))
      (node (ref "U3") (pin "10") (pinfunction "PC6_10") (pintype "bidirectional"))
    )
    (net (code "58") (name "Net-(U3-PD6)") (class "Default")
      (node (ref "TP2") (pin "TP") (pinfunction "TP_TP") (pintype "input"))
      (node (ref "U3") (pin "22") (pinfunction "PD6_22") (pintype "bidirectional"))
    )
    (net (code "59") (name "Net-(U3-PD7)") (class "Default")
      (node (ref "TP1") (pin "TP") (pinfunction "TP_TP") (pintype "input"))
      (node (ref "U3") (pin "21") (pinfunction "PD7_21") (pintype "bidirectional"))
    )
    (net (code "60") (name "Net-(U4-RX)") (class "Default")
      (node (ref "J2") (pin "3") (pinfunction "3_3") (pintype "bidirectional"))
      (node (ref "U4") (pin "RXD") (pinfunction "RX_RXD") (pintype "bidirectional"))
    )
    (net (code "61") (name "Net-(U4-TX)") (class "Default")
      (node (ref "J2") (pin "2") (pinfunction "2_2") (pintype "bidirectional"))
      (node (ref "U4") (pin "TXD") (pinfunction "TX_TXD") (pintype "bidirectional"))
    )
    (net (code "62") (name "ROW0") (class "Default")
      (node (ref "R23") (pin "1") (pinfunction "1_1") (pintype "passive"))
      (node (ref "U3") (pin "25") (pinfunction "PD3_25") (pintype "bidirectional"))
    )
    (net (code "63") (name "ROW1") (class "Default")
      (node (ref "R24") (pin "1") (pinfunction "1_1") (pintype "passive"))
      (node (ref "U3") (pin "26") (pinfunction "PD2_26") (pintype "bidirectional"))
    )
    (net (code "64") (name "ROW2") (class "Default")
      (node (ref "R25") (pin "1") (pinfunction "1_1") (pintype "passive"))
      (node (ref "U3") (pin "27") (pinfunction "PD1_27") (pintype "bidirectional"))
    )
    (net (code "65") (name "ROW3") (class "Default")
      (node (ref "R26") (pin "1") (pinfunction "1_1") (pintype "passive"))
      (node (ref "U3") (pin "28") (pinfunction "PD0_28") (pintype "bidirectional"))
    )
    (net (code "66") (name "RST") (class "Default")
      (node (ref "R16") (pin "1") (pinfunction "1_1") (pintype "passive"))
      (node (ref "SWT2") (pin "2") (pinfunction "P$2_2") (pintype "bidirectional"))
      (node (ref "TP3") (pin "TP") (pinfunction "TP_TP") (pintype "input"))
      (node (ref "U3") (pin "24") (pinfunction "PD4_24") (pintype "bidirectional"))
      (node (ref "U4") (pin "RST") (pinfunction "RST_RST") (pintype "bidirectional"))
    )
    (net (code "67") (name "SCL") (class "Default")
      (node (ref "R21") (pin "1") (pinfunction "1_1") (pintype "passive"))
      (node (ref "TP9") (pin "TP") (pinfunction "TP_TP") (pintype "input"))
      (node (ref "U3") (pin "15") (pinfunction "PC1_15") (pintype "bidirectional"))
      (node (ref "U4") (pin "IO5") (pinfunction "IO5_IO5") (pintype "bidirectional"))
      (node (ref "U5") (pin "2") (pinfunction "SCL_2") (pintype "bidirectional"))
      (node (ref "U7") (pin "4") (pinfunction "SCL_4") (pintype "bidirectional"))
    )
    (net (code "68") (name "SDA") (class "Default")
      (node (ref "R18") (pin "1") (pinfunction "1_1") (pintype "passive"))
      (node (ref "TP8") (pin "TP") (pinfunction "TP_TP") (pintype "input"))
      (node (ref "U3") (pin "16") (pinfunction "PC0_16") (pintype "bidirectional"))
      (node (ref "U4") (pin "IO4") (pinfunction "IO4_IO4") (pintype "bidirectional"))
      (node (ref "U5") (pin "6") (pinfunction "SDA_6") (pintype "bidirectional"))
      (node (ref "U7") (pin "3") (pinfunction "SDA_3") (pintype "bidirectional"))
    )
    (net (code "69") (name "unconnected-(J2-Pad1)") (class "Default")
      (node (ref "J2") (pin "1") (pinfunction "1_1") (pintype "bidirectional"))
    )
    (net (code "70") (name "unconnected-(J2-Pad4)") (class "Default")
      (node (ref "J2") (pin "4") (pinfunction "4_4") (pintype "bidirectional"))
    )
    (net (code "71") (name "unconnected-(J2-Pad5)") (class "Default")
      (node (ref "J2") (pin "5") (pinfunction "5_5") (pintype "bidirectional"))
    )
    (net (code "72") (name "unconnected-(J3-Pad3)") (class "Default")
      (node (ref "J3") (pin "3") (pinfunction "3_3") (pintype "bidirectional"))
    )
    (net (code "73") (name "unconnected-(J3-Pad4)") (class "Default")
      (node (ref "J3") (pin "4") (pinfunction "4_4") (pintype "bidirectional"))
    )
    (net (code "74") (name "unconnected-(U3-PC3-Pad13)") (class "Default")
      (node (ref "U3") (pin "13") (pinfunction "PC3_13") (pintype "bidirectional"))
    )
    (net (code "75") (name "unconnected-(U3-PC7-Pad9)") (class "Default")
      (node (ref "U3") (pin "9") (pinfunction "PC7_9") (pintype "bidirectional"))
    )
    (net (code "76") (name "unconnected-(U3-PR0-Pad20)") (class "Default")
      (node (ref "U3") (pin "20") (pinfunction "PR0_20") (pintype "bidirectional"))
    )
    (net (code "77") (name "unconnected-(U3-PR1-Pad19)") (class "Default")
      (node (ref "U3") (pin "19") (pinfunction "PR1_19") (pintype "bidirectional"))
    )
    (net (code "78") (name "unconnected-(U5-INT-Pad5)") (class "Default")
      (node (ref "U5") (pin "5") (pinfunction "INT_5") (pintype "bidirectional"))
    )
  )
)
